# H0FR9.net
KiCad netlist of a schematic drawn in EAGLE
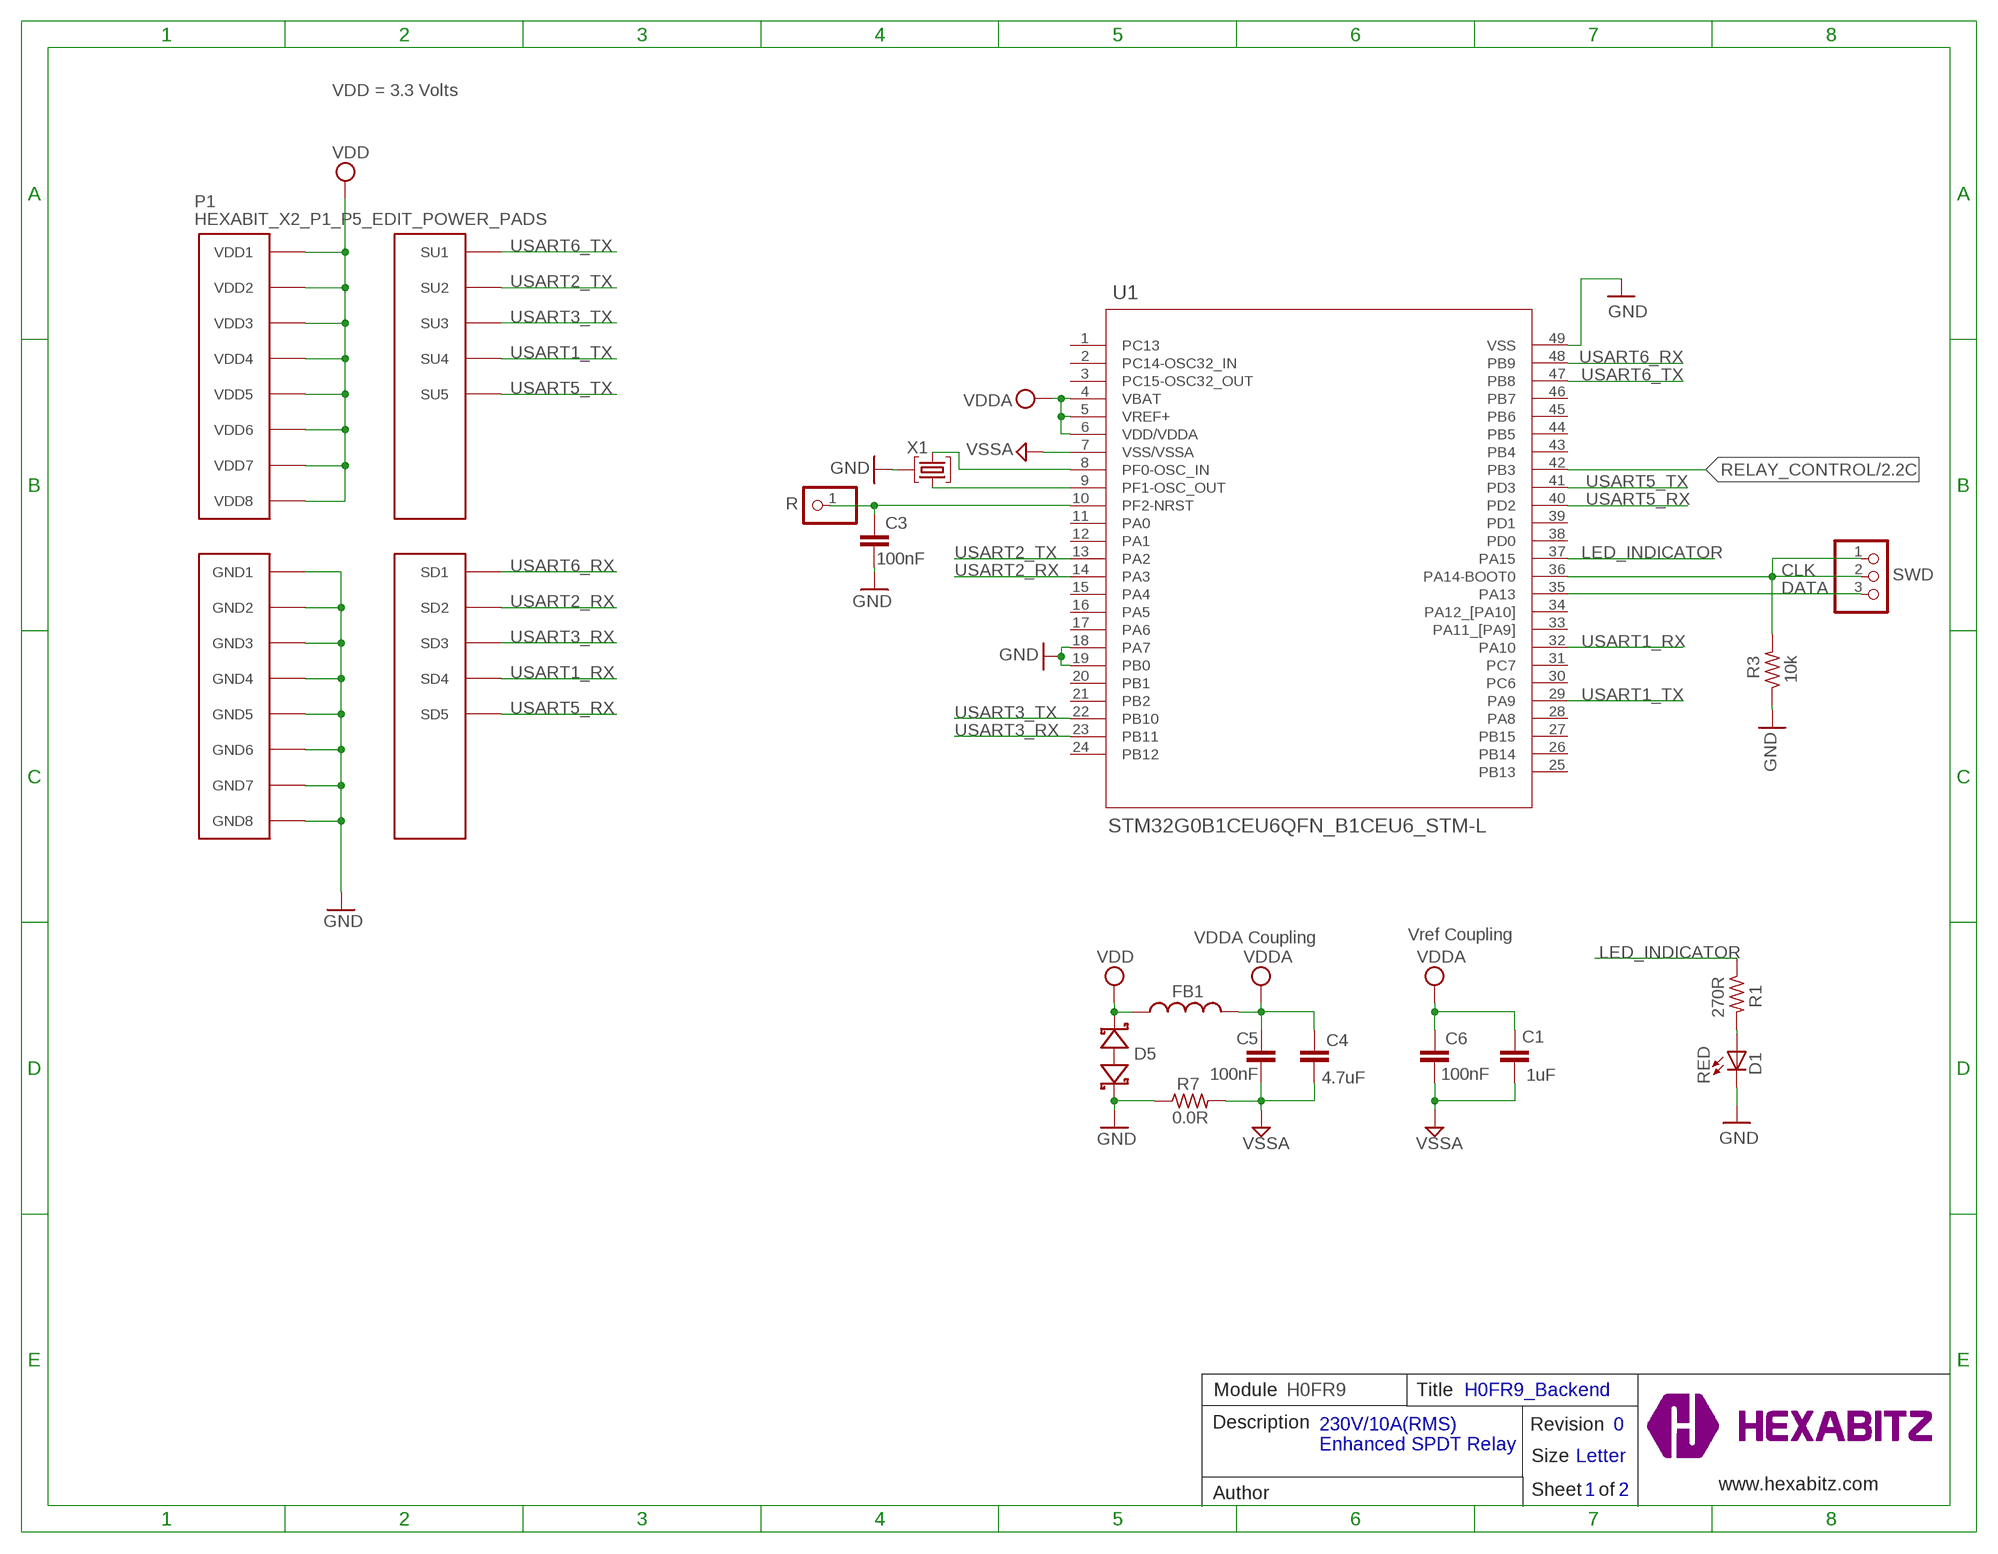
[diagram p0: schematic, sheet 1]
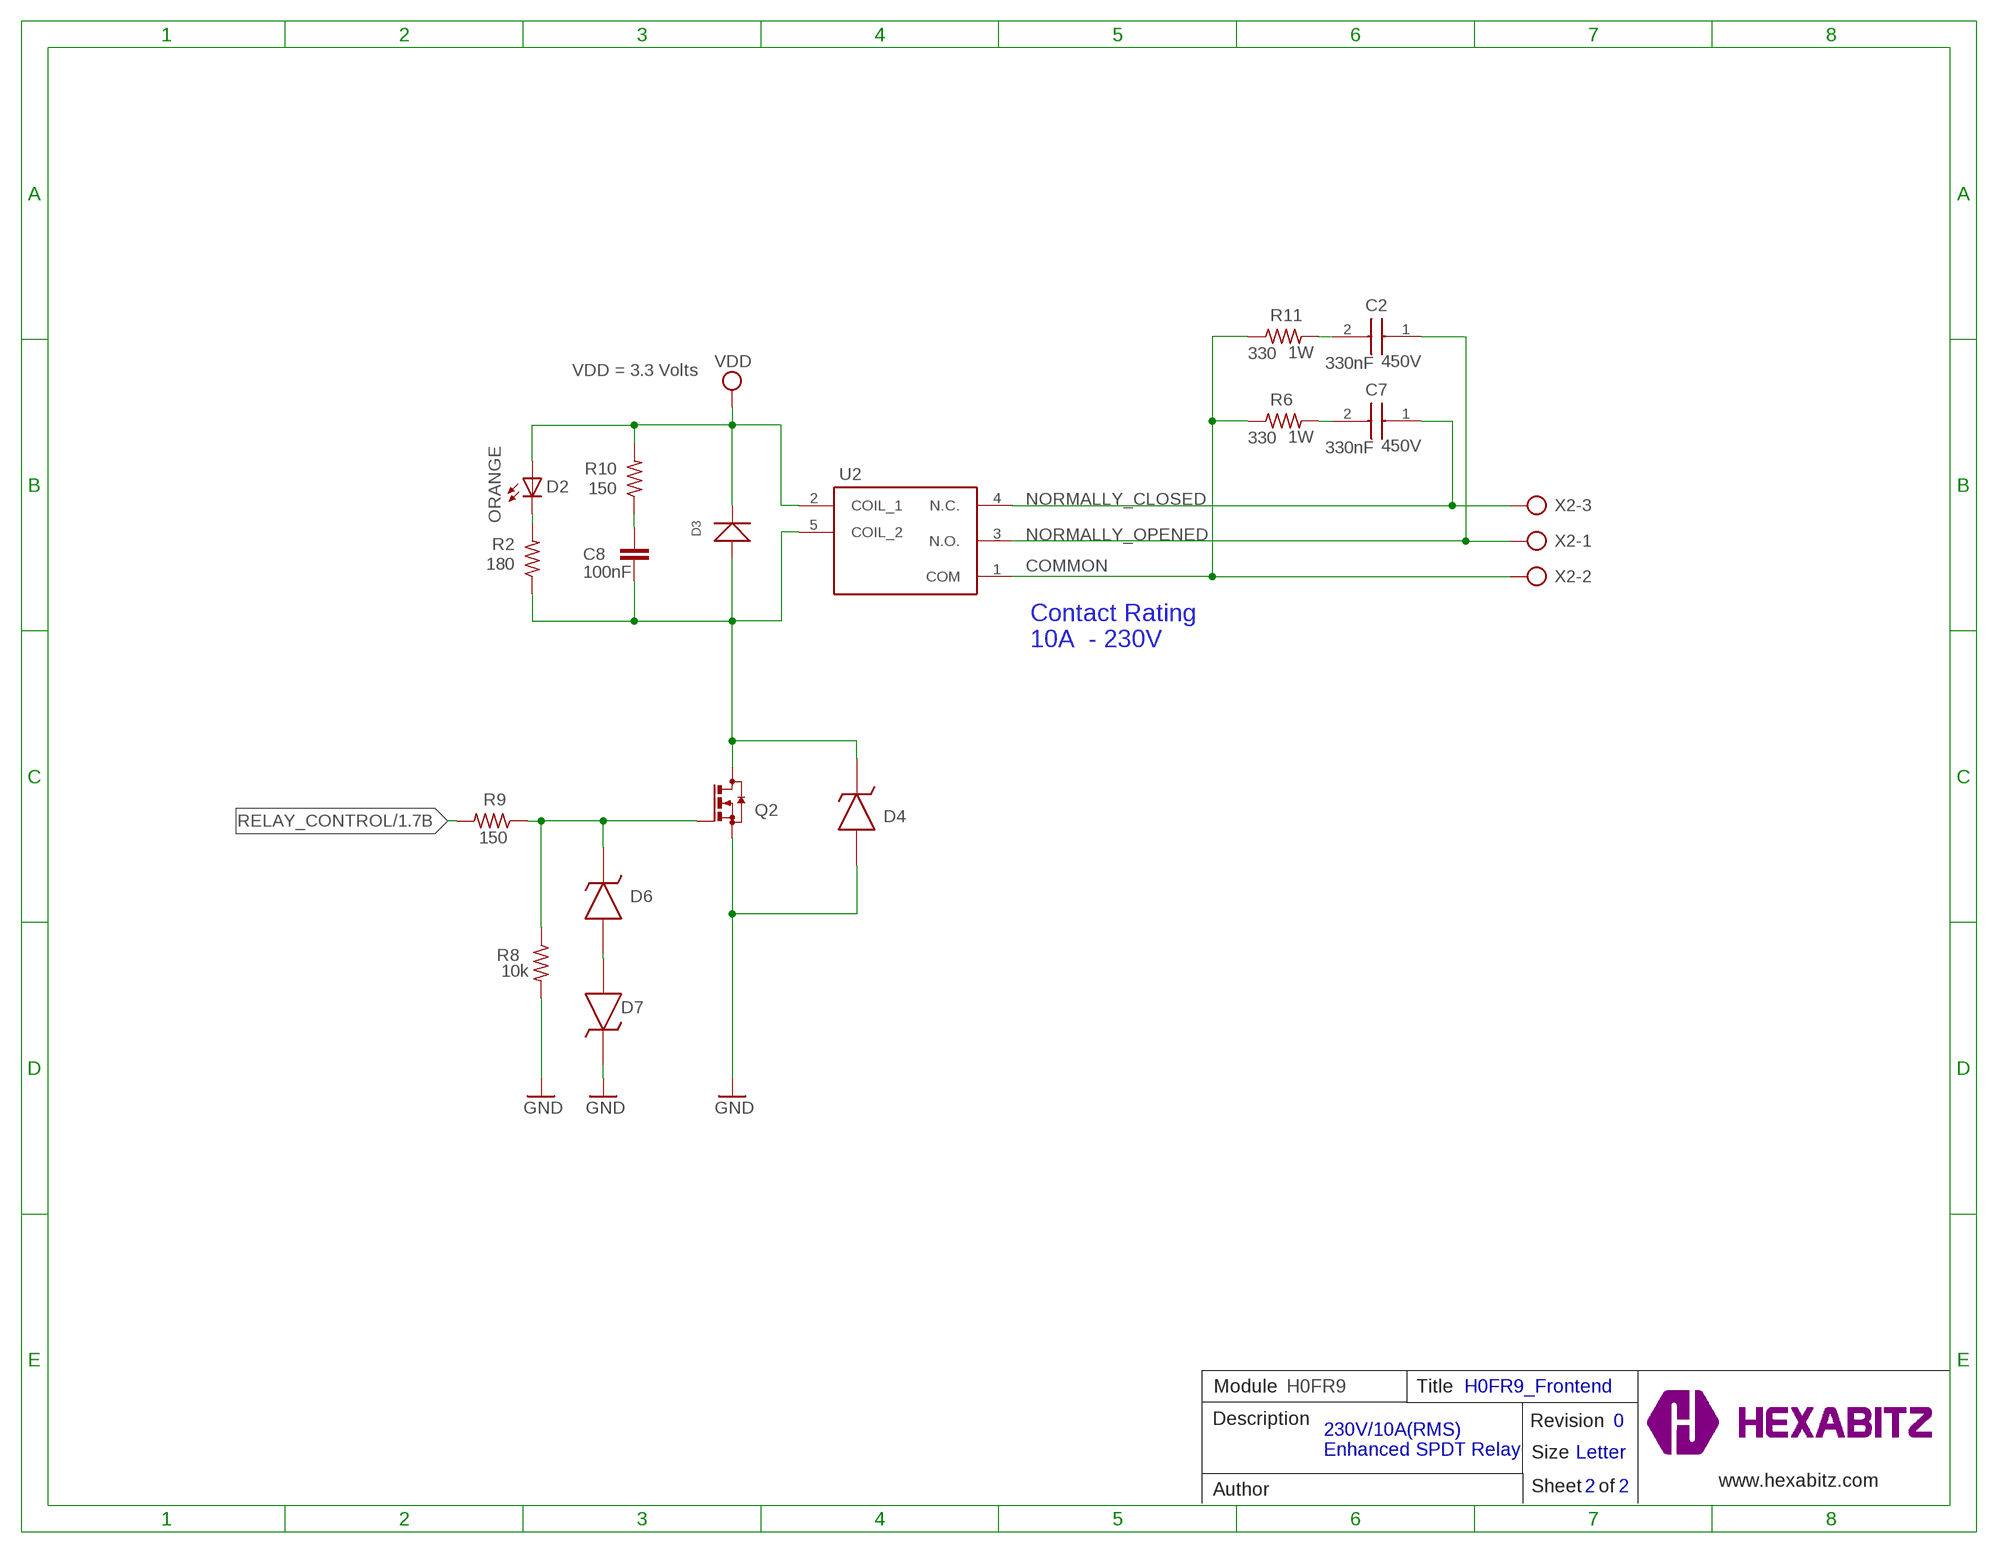
[diagram p1: schematic, sheet 2]

(export (version "E")
  (design (tool "Eeschema 10.0.6"))
  (components
    (comp (ref "C2")
      (value "330nF")
      (footprint "eagle-import:B32922Q_(18_X_8.5)")
      (fields
        (field (name "MANUFACTURER_PART_NUMBER") "B32922Q3334K000")
        (field (name "MOUSER_PART_NUMBER") "871-B32922Q3334K000")
        (field (name "VOLTAAGE") "450V")
      )
      (libsource (lib "eagle-import") (part "B32922Q3334K000"))
    )
    (comp (ref "C7")
      (value "330nF")
      (footprint "eagle-import:B32922Q_(18_X_8.5)")
      (fields
        (field (name "MANUFACTURER_PART_NUMBER") "B32922Q3334K000")
        (field (name "MOUSER_PART_NUMBER") "871-B32922Q3334K000")
        (field (name "VOLTAAGE") "450V")
      )
      (libsource (lib "eagle-import") (part "B32922Q3334K000"))
    )
    (comp (ref "C8")
      (value "100nF")
      (footprint "eagle-import:C-0603")
      (fields
        (field (name "CAPACITANCE") "100nF")
        (field (name "MFN") "KEMET")
        (field (name "MPN") "C0603C104K8RACTU")
        (field (name "OCTOPART_URL") "https://octopart.com/c0603c104k8ractu-kemet-145075?r=sp&s=9bS9ASSwSEqMCE9KBEQZ0g")
        (field (name "TOLERANCE") "10%")
        (field (name "VOLTAGE_RATING") "10V")
      )
      (libsource (lib "eagle-import") (part "C-0603"))
    )
    (comp (ref "D2")
      (value "ORANGE")
      (footprint "eagle-import:VLMS1300-GS08")
      (fields
        (field (name "MPN") "VLMS1300-GS08")
        (field (name "COULOR") "ORANGE")
        (field (name "MFN") "Vishay ")
        (field (name "MPN_1") "VLMY1300-GS08")
        (field (name "OCTOPART_URL") "https://octopart.com/vlmy1300-gs08-vishay-21709204")
      )
      (libsource (lib "eagle-import") (part "Hexabitz_VLMS1300-GS08"))
    )
    (comp (ref "D3")
      (value "40V 300MA")
      (footprint "eagle-import:SOD-323")
      (fields (field (name "MPN") "BAT54JFILM"))
      (libsource (lib "eagle-import") (part "BAT54JFILM_SOD-323"))
    )
    (comp (ref "D4")
      (value "MMSZ4705T1GMMSZ4705T1G")
      (footprint "eagle-import:DIO_MMSZ4700T1G")
      (fields (field (name "MPN") "MMSZ4705T1G"))
      (libsource (lib "eagle-import") (part "MMSZ4705T1GMMSZ4705T1G"))
    )
    (comp (ref "D6")
      (value "MMSZ4705T1GMMSZ4705T1G")
      (footprint "eagle-import:DIO_MMSZ4700T1G")
      (fields (field (name "MPN") "MMSZ5231BT3G"))
      (libsource (lib "eagle-import") (part "MMSZ4705T1GMMSZ4705T1G"))
    )
    (comp (ref "D7")
      (value "MMSZ4705T1GMMSZ4705T1G")
      (footprint "eagle-import:DIO_MMSZ4700T1G")
      (fields (field (name "MPN") "MMSZ5231BT3G"))
      (libsource (lib "eagle-import") (part "MMSZ4705T1GMMSZ4705T1G"))
    )
    (comp (ref "Q2")
      (value "BSS123")
      (footprint "eagle-import:SOT23")
      (libsource (lib "eagle-import") (part "BSS123"))
    )
    (comp (ref "R2")
      (value "180")
      (footprint "eagle-import:R-0603")
      (fields
        (field (name "MFN") "Panasonic")
        (field (name "MPN") "ERJ-3GEYJ181V")
        (field (name "OCTOPART_URL") "https://octopart.com/erj-3geyj181v-panasonic-55403673")
        (field (name "RESISTANCE") "180.0 Ω")
        (field (name "TOLERANCE") "±5%")
      )
      (libsource (lib "eagle-import") (part "R-0603"))
    )
    (comp (ref "R6")
      (value "330")
      (footprint "eagle-import:R2512")
      (fields (field (name "MPN") "RMCF2512JT330R") (field (name "POWER") "1W"))
      (libsource (lib "eagle-import") (part "R-US_R2512"))
    )
    (comp (ref "R8")
      (value "10k")
      (footprint "eagle-import:R-0603")
      (fields
        (field (name "MFN") "Yageo")
        (field (name "MPN") "RC0603JR-07680KL")
        (field (name "OCTOPART_URL") "https://octopart.com/rc0603jr-07680kl-yageo-40953169?r=sp")
        (field (name "RESISTANCE") "680K Ohm")
        (field (name "TOLERANCE") "5%")
      )
      (libsource (lib "eagle-import") (part "R-0603"))
    )
    (comp (ref "R9")
      (value "150")
      (footprint "eagle-import:R-0603")
      (fields
        (field (name "MFN") "Yageo")
        (field (name "MPN") "RC0603JR-07680KL")
        (field (name "OCTOPART_URL") "https://octopart.com/rc0603jr-07680kl-yageo-40953169?r=sp")
        (field (name "RESISTANCE") "680K Ohm")
        (field (name "TOLERANCE") "5%")
      )
      (libsource (lib "eagle-import") (part "R-0603"))
    )
    (comp (ref "R10")
      (value "150")
      (footprint "eagle-import:R-0603")
      (fields
        (field (name "MFN") "Yageo")
        (field (name "MPN") "RC0603JR-07680KL")
        (field (name "OCTOPART_URL") "https://octopart.com/rc0603jr-07680kl-yageo-40953169?r=sp")
        (field (name "RESISTANCE") "680K Ohm")
        (field (name "TOLERANCE") "5%")
      )
      (libsource (lib "eagle-import") (part "R-0603"))
    )
    (comp (ref "R11")
      (value "330")
      (footprint "eagle-import:R2512")
      (fields (field (name "MPN") "RMCF2512JT330R") (field (name "POWER") "1W"))
      (libsource (lib "eagle-import") (part "R-US_R2512"))
    )
    (comp (ref "U2")
      (value "G5LE-14_DC3")
      (footprint "eagle-import:G5LE-14_SPDT")
      (fields
        (field (name "MANUFACTURER_PART_NUMBER") "G5LE-14 DC3")
        (field (name "MOUSER_PART_NUMBER") "653-G5LE-14DC3")
      )
      (libsource (lib "eagle-import") (part "G5LE-14_DC3"))
    )
    (comp (ref "X2")
      (value "AK300/3")
      (footprint "eagle-import:AK300_3")
      (fields (field (name "MPN") "1715734"))
      (libsource (lib "eagle-import") (part "AK300/3"))
    )
    (comp (ref "C1")
      (value "1uF")
      (footprint "eagle-import:C-0805")
      (fields
        (field (name "CAPACITANCE") "1.00uF")
        (field (name "MFN") "Yageo")
        (field (name "MPN") "CC0805KKX7R7BB105")
        (field (name "OCTOPART_URL") "https://octopart.com/cc0805kkx7r7bb105-yageo-8376555?r=sp&s=YKl1wwtkROau_X5nniH2ig")
        (field (name "TOLERANCE") "10%")
        (field (name "VOLTAGE_RATING") "16V")
      )
      (libsource (lib "eagle-import") (part "C-0805"))
    )
    (comp (ref "C3")
      (value "100nF")
      (footprint "eagle-import:C-0603")
      (libsource (lib "eagle-import") (part "C-0603"))
    )
    (comp (ref "C4")
      (value "4.7uF")
      (footprint "eagle-import:C-0805")
      (fields
        (field (name "CAPACITANCE") "4.7uF")
        (field (name "MFN") "Murata")
        (field (name "MPN") "GRM21BC81E475KA12L")
        (field (name "OCTOPART_URL") "https://octopart.com/grm21bc81e475ka12l-murata-10331911?r=sp&s=RY3qZSD8T6mG6TC9CHI5qQ")
        (field (name "TOLERANCE") "10%")
        (field (name "VOLTAGE_RATING") "25V")
      )
      (libsource (lib "eagle-import") (part "C-0805"))
    )
    (comp (ref "C5")
      (value "100nF")
      (footprint "eagle-import:C-0603")
      (libsource (lib "eagle-import") (part "C-0603"))
    )
    (comp (ref "C6")
      (value "100nF")
      (footprint "eagle-import:C-0603")
      (fields
        (field (name "CAPACITANCE") "100nF")
        (field (name "MFN") "KEMET")
        (field (name "MPN") "C0603C104K8RACTU")
        (field (name "OCTOPART_URL") "https://octopart.com/c0603c104k8ractu-kemet-145075?r=sp&s=9bS9ASSwSEqMCE9KBEQZ0g")
        (field (name "TOLERANCE") "10%")
        (field (name "VOLTAGE_RATING") "10V")
      )
      (libsource (lib "eagle-import") (part "C-0603"))
    )
    (comp (ref "D1")
      (value "RED")
      (footprint "eagle-import:VLMS1300-GS08")
      (fields
        (field (name "MPN") "VLMS1300-GS08")
        (field (name "MFN") "Vishay")
        (field (name "MPN_1") "VLMS1300-GS08")
        (field (name "OCTOPART_URL") "https://octopart.com/vlms1300-gs08-vishay-21709201?r=sp&s=_gcP4_q8T1SC6PJQPTQ9yA")
      )
      (libsource (lib "eagle-import") (part "VLMS1300-GS08"))
    )
    (comp (ref "D5")
      (value "BOURNS_CDSOD323-T03SCBOURNS_CDSOD323-T03SC_0_0")
      (footprint "eagle-import:BOURNS_CDSOD323-T03SC_0")
      (fields (field (name "MPN") "CDSOD323-T03SC"))
      (libsource (lib "eagle-import") (part "BOURNS_CDSOD323-T03SCBOURNS_CDSOD323-T03SC_0_0"))
    )
    (comp (ref "FB1")
      (value "FB-0603")
      (footprint "eagle-import:FB-0603")
      (libsource (lib "eagle-import") (part "FB-0603"))
    )
    (comp (ref "P1")
      (value "HEXABIT_X2_P1_P5_EDIT_POWER_PADS")
      (footprint "eagle-import:HEXABIT_X2_P1_P5_EDIT_POWER_PADS")
      (libsource (lib "eagle-import") (part "HEXABIT_X2_P1_P5_EDIT_POWER_PADS"))
    )
    (comp (ref "R")
      (value "R")
      (footprint "eagle-import:1X01")
      (fields (field (name "MPN") "87227-1"))
      (libsource (lib "eagle-import") (part "PINHD-1X1"))
    )
    (comp (ref "R1")
      (value "270R")
      (footprint "eagle-import:R-0603")
      (libsource (lib "eagle-import") (part "R-0603"))
    )
    (comp (ref "R3")
      (value "10k")
      (footprint "eagle-import:R-0603")
      (fields
        (field (name "MFN") "Yageo")
        (field (name "MPN") "RC0603JR-0710KL")
        (field (name "OCTOPART_URL") "https://octopart.com/search?q=RC0603JR-0710KL&start=0")
        (field (name "RESISTANCE") "10.0K Ohm")
        (field (name "TOLERANCE") "5%")
      )
      (libsource (lib "eagle-import") (part "R-0603"))
    )
    (comp (ref "R7")
      (value "0.0R")
      (footprint "eagle-import:R-0603")
      (libsource (lib "eagle-import") (part "R-0603"))
    )
    (comp (ref "SWD")
      (value "PINHD-1X3SWD")
      (footprint "eagle-import:SWD")
      (libsource (lib "eagle-import") (part "PINHD-1X3SWD"))
    )
    (comp (ref "TRIMBLE-LOGO2")
      (value "HEXA-LOGO")
      (footprint "eagle-import:HEXA-LOGO")
      (libsource (lib "eagle-import") (part "HEXA-LOGO"))
    )
    (comp (ref "U1")
      (value "STM32G0B1CEU6QFN_B1CEU6_STM-L")
      (footprint "eagle-import:QFN_B1CEU6_STM-L")
      (fields
        (field (name "MANUFACTURER_PART_NUMBER") "STM32G0B1CEU6")
        (field (name "COPYRIGHT") "Copyright (C) 2021 Ultra Librarian. All rights reserved.")
      )
      (libsource (lib "eagle-import") (part "STM32G0B1CEU6QFN_B1CEU6_STM-L"))
    )
    (comp (ref "X1")
      (value "XTALL_CSTCE8M00G52")
      (footprint "eagle-import:XTALL_CSTCE8M00G52")
      (fields (field (name "MPN") "CSTCE8M00G52Z-R0"))
      (libsource (lib "eagle-import") (part "XTALL_CSTCE8M00G52"))
    )
  )
  (nets
    (net (code "1") (name "CLK") (class "Default")
      (node (ref "R3") (pin "2") (pinfunction "2_2") (pintype "passive"))
      (node (ref "SWD") (pin "1") (pinfunction "1_1") (pintype "passive"))
      (node (ref "SWD") (pin "2") (pinfunction "2_2") (pintype "passive"))
      (node (ref "U1") (pin "36") (pinfunction "PA14-BOOT0_36") (pintype "bidirectional"))
    )
    (net (code "2") (name "COMMON") (class "Default")
      (node (ref "R11") (pin "1") (pinfunction "1_1") (pintype "passive"))
      (node (ref "R6") (pin "1") (pinfunction "1_1") (pintype "passive"))
      (node (ref "U2") (pin "1") (pinfunction "COM_1") (pintype "bidirectional"))
      (node (ref "X2") (pin "2") (pinfunction "KL_2") (pintype "passive"))
    )
    (net (code "3") (name "DATA") (class "Default")
      (node (ref "SWD") (pin "3") (pinfunction "3_3") (pintype "passive"))
      (node (ref "U1") (pin "35") (pinfunction "PA13_35") (pintype "bidirectional"))
    )
    (net (code "4") (name "GND") (class "Default")
      (node (ref "C3") (pin "2") (pinfunction "2_2") (pintype "passive"))
      (node (ref "D1") (pin "C") (pinfunction "C_C") (pintype "passive"))
      (node (ref "D4") (pin "A") (pinfunction "A_A") (pintype "bidirectional"))
      (node (ref "D5") (pin "2") (pinfunction "C_2") (pintype "passive"))
      (node (ref "D7") (pin "K") (pinfunction "K_K") (pintype "bidirectional"))
      (node (ref "P1") (pin "PAD_PD11") (pinfunction "GND1_PAD_PD11") (pintype "power_in"))
      (node (ref "P1") (pin "PAD_PD12") (pinfunction "GND2_PAD_PD12") (pintype "power_in"))
      (node (ref "P1") (pin "PAD_PD13") (pinfunction "GND3_PAD_PD13") (pintype "power_in"))
      (node (ref "P1") (pin "PAD_PD14") (pinfunction "GND4_PAD_PD14") (pintype "power_in"))
      (node (ref "P1") (pin "PAD_PD17") (pinfunction "GND5_PAD_PD17") (pintype "power_in"))
      (node (ref "P1") (pin "PAD_PD18") (pinfunction "GND6_PAD_PD18") (pintype "power_in"))
      (node (ref "P1") (pin "PAD_PD19") (pinfunction "GND7_PAD_PD19") (pintype "power_in"))
      (node (ref "P1") (pin "PAD_PD20") (pinfunction "GND8_PAD_PD20") (pintype "power_in"))
      (node (ref "Q2") (pin "2") (pinfunction "S_2") (pintype "passive"))
      (node (ref "R3") (pin "1") (pinfunction "1_1") (pintype "passive"))
      (node (ref "R7") (pin "1") (pinfunction "1_1") (pintype "passive"))
      (node (ref "R8") (pin "2") (pinfunction "2_2") (pintype "passive"))
      (node (ref "U1") (pin "18") (pinfunction "PA7_18") (pintype "bidirectional"))
      (node (ref "U1") (pin "19") (pinfunction "PB0_19") (pintype "bidirectional"))
      (node (ref "U1") (pin "49") (pinfunction "VSS_49") (pintype "passive"))
      (node (ref "X1") (pin "P$2") (pinfunction "2_P$2") (pintype "passive"))
    )
    (net (code "5") (name "LED_INDICATOR") (class "Default")
      (node (ref "R1") (pin "1") (pinfunction "1_1") (pintype "passive"))
      (node (ref "U1") (pin "37") (pinfunction "PA15_37") (pintype "bidirectional"))
    )
    (net (code "6") (name "NORMALLY_CLOSED") (class "Default")
      (node (ref "C7") (pin "1") (pinfunction "1_1") (pintype "bidirectional"))
      (node (ref "U2") (pin "4") (pinfunction "N.C._4") (pintype "bidirectional"))
      (node (ref "X2") (pin "3") (pinfunction "KL_3") (pintype "passive"))
    )
    (net (code "7") (name "NORMALLY_OPENED") (class "Default")
      (node (ref "C2") (pin "1") (pinfunction "1_1") (pintype "bidirectional"))
      (node (ref "U2") (pin "3") (pinfunction "N.O._3") (pintype "bidirectional"))
      (node (ref "X2") (pin "1") (pinfunction "KL_1") (pintype "passive"))
    )
    (net (code "8") (name "Net-(C2-Pad2)") (class "Default")
      (node (ref "C2") (pin "2") (pinfunction "2_2") (pintype "bidirectional"))
      (node (ref "R11") (pin "2") (pinfunction "2_2") (pintype "passive"))
    )
    (net (code "9") (name "Net-(C7-Pad2)") (class "Default")
      (node (ref "C7") (pin "2") (pinfunction "2_2") (pintype "bidirectional"))
      (node (ref "R6") (pin "2") (pinfunction "2_2") (pintype "passive"))
    )
    (net (code "10") (name "Net-(C8-Pad1)") (class "Default")
      (node (ref "C8") (pin "1") (pinfunction "1_1") (pintype "passive"))
      (node (ref "R10") (pin "1") (pinfunction "1_1") (pintype "passive"))
    )
    (net (code "11") (name "Net-(D1-PadA)") (class "Default")
      (node (ref "D1") (pin "A") (pinfunction "A_A") (pintype "passive"))
      (node (ref "R1") (pin "2") (pinfunction "2_2") (pintype "passive"))
    )
    (net (code "12") (name "Net-(D2-PadC)") (class "Default")
      (node (ref "D2") (pin "C") (pinfunction "C_C") (pintype "passive"))
      (node (ref "R2") (pin "2") (pinfunction "2_2") (pintype "passive"))
    )
    (net (code "13") (name "Net-(D6-PadA)") (class "Default")
      (node (ref "D6") (pin "A") (pinfunction "A_A") (pintype "bidirectional"))
      (node (ref "D7") (pin "A") (pinfunction "A_A") (pintype "bidirectional"))
    )
    (net (code "14") (name "Net-(Q2-D)") (class "Default")
      (node (ref "C8") (pin "2") (pinfunction "2_2") (pintype "passive"))
      (node (ref "D3") (pin "+") (pinfunction "+_+") (pintype "passive"))
      (node (ref "D4") (pin "K") (pinfunction "K_K") (pintype "bidirectional"))
      (node (ref "Q2") (pin "3") (pinfunction "D_3") (pintype "passive"))
      (node (ref "R2") (pin "1") (pinfunction "1_1") (pintype "passive"))
      (node (ref "U2") (pin "5") (pinfunction "COIL_2_5") (pintype "bidirectional"))
    )
    (net (code "15") (name "Net-(Q2-G)") (class "Default")
      (node (ref "D6") (pin "K") (pinfunction "K_K") (pintype "bidirectional"))
      (node (ref "Q2") (pin "1") (pinfunction "G_1") (pintype "passive"))
      (node (ref "R8") (pin "1") (pinfunction "1_1") (pintype "passive"))
      (node (ref "R9") (pin "1") (pinfunction "1_1") (pintype "passive"))
    )
    (net (code "16") (name "Net-(U1-PF0-OSC_IN)") (class "Default")
      (node (ref "U1") (pin "8") (pinfunction "PF0-OSC_IN_8") (pintype "bidirectional"))
      (node (ref "X1") (pin "P$3") (pinfunction "3_P$3") (pintype "passive"))
    )
    (net (code "17") (name "Net-(U1-PF1-OSC_OUT)") (class "Default")
      (node (ref "U1") (pin "9") (pinfunction "PF1-OSC_OUT_9") (pintype "output"))
      (node (ref "X1") (pin "P$1") (pinfunction "1_P$1") (pintype "passive"))
    )
    (net (code "18") (name "Net-(U1-PF2-NRST)") (class "Default")
      (node (ref "C3") (pin "1") (pinfunction "1_1") (pintype "passive"))
      (node (ref "R") (pin "1") (pinfunction "1_1") (pintype "passive"))
      (node (ref "U1") (pin "10") (pinfunction "PF2-NRST_10") (pintype "bidirectional"))
    )
    (net (code "19") (name "RELAY_CONTROL") (class "Default")
      (node (ref "R9") (pin "2") (pinfunction "2_2") (pintype "passive"))
      (node (ref "U1") (pin "42") (pinfunction "PB3_42") (pintype "bidirectional"))
    )
    (net (code "20") (name "USART1_RX") (class "Default")
      (node (ref "P1") (pin "PAD_PD4") (pinfunction "SD4_PAD_PD4") (pintype "bidirectional"))
      (node (ref "U1") (pin "32") (pinfunction "PA10_32") (pintype "bidirectional"))
    )
    (net (code "21") (name "USART1_TX") (class "Default")
      (node (ref "P1") (pin "PAD_PU4") (pinfunction "SU4_PAD_PU4") (pintype "bidirectional"))
      (node (ref "U1") (pin "29") (pinfunction "PA9_29") (pintype "bidirectional"))
    )
    (net (code "22") (name "USART2_RX") (class "Default")
      (node (ref "P1") (pin "PAD_PD2") (pinfunction "SD2_PAD_PD2") (pintype "bidirectional"))
      (node (ref "U1") (pin "14") (pinfunction "PA3_14") (pintype "bidirectional"))
    )
    (net (code "23") (name "USART2_TX") (class "Default")
      (node (ref "P1") (pin "PAD_PU2") (pinfunction "SU2_PAD_PU2") (pintype "bidirectional"))
      (node (ref "U1") (pin "13") (pinfunction "PA2_13") (pintype "bidirectional"))
    )
    (net (code "24") (name "USART3_RX") (class "Default")
      (node (ref "P1") (pin "PAD_PD3") (pinfunction "SD3_PAD_PD3") (pintype "bidirectional"))
      (node (ref "U1") (pin "23") (pinfunction "PB11_23") (pintype "bidirectional"))
    )
    (net (code "25") (name "USART3_TX") (class "Default")
      (node (ref "P1") (pin "PAD_PU3") (pinfunction "SU3_PAD_PU3") (pintype "bidirectional"))
      (node (ref "U1") (pin "22") (pinfunction "PB10_22") (pintype "bidirectional"))
    )
    (net (code "26") (name "USART5_RX") (class "Default")
      (node (ref "P1") (pin "PAD_PD5") (pinfunction "SD5_PAD_PD5") (pintype "bidirectional"))
      (node (ref "U1") (pin "40") (pinfunction "PD2_40") (pintype "bidirectional"))
    )
    (net (code "27") (name "USART5_TX") (class "Default")
      (node (ref "P1") (pin "PAD_PU5") (pinfunction "SU5_PAD_PU5") (pintype "bidirectional"))
      (node (ref "U1") (pin "41") (pinfunction "PD3_41") (pintype "bidirectional"))
    )
    (net (code "28") (name "USART6_RX") (class "Default")
      (node (ref "P1") (pin "PAD_PD1") (pinfunction "SD1_PAD_PD1") (pintype "bidirectional"))
      (node (ref "U1") (pin "48") (pinfunction "PB9_48") (pintype "bidirectional"))
    )
    (net (code "29") (name "USART6_TX") (class "Default")
      (node (ref "P1") (pin "PAD_PU1") (pinfunction "SU1_PAD_PU1") (pintype "bidirectional"))
      (node (ref "U1") (pin "47") (pinfunction "PB8_47") (pintype "bidirectional"))
    )
    (net (code "30") (name "VDD") (class "Default")
      (node (ref "D2") (pin "A") (pinfunction "A_A") (pintype "passive"))
      (node (ref "D3") (pin "-") (pinfunction "-_-") (pintype "passive"))
      (node (ref "D5") (pin "1") (pinfunction "A_1") (pintype "passive"))
      (node (ref "FB1") (pin "1") (pinfunction "1_1") (pintype "passive"))
      (node (ref "P1") (pin "PAD_PU11") (pinfunction "VDD1_PAD_PU11") (pintype "power_in"))
      (node (ref "P1") (pin "PAD_PU12") (pinfunction "VDD2_PAD_PU12") (pintype "power_in"))
      (node (ref "P1") (pin "PAD_PU13") (pinfunction "VDD3_PAD_PU13") (pintype "power_in"))
      (node (ref "P1") (pin "PAD_PU14") (pinfunction "VDD4_PAD_PU14") (pintype "power_in"))
      (node (ref "P1") (pin "PAD_PU17") (pinfunction "VDD5_PAD_PU17") (pintype "power_in"))
      (node (ref "P1") (pin "PAD_PU18") (pinfunction "VDD6_PAD_PU18") (pintype "power_in"))
      (node (ref "P1") (pin "PAD_PU19") (pinfunction "VDD7_PAD_PU19") (pintype "power_in"))
      (node (ref "P1") (pin "PAD_PU20") (pinfunction "VDD8_PAD_PU20") (pintype "power_in"))
      (node (ref "R10") (pin "2") (pinfunction "2_2") (pintype "passive"))
      (node (ref "U2") (pin "2") (pinfunction "COIL_1_2") (pintype "bidirectional"))
    )
    (net (code "31") (name "VDDA") (class "Default")
      (node (ref "C1") (pin "1") (pinfunction "1_1") (pintype "passive"))
      (node (ref "C4") (pin "1") (pinfunction "1_1") (pintype "passive"))
      (node (ref "C5") (pin "1") (pinfunction "1_1") (pintype "passive"))
      (node (ref "C6") (pin "1") (pinfunction "1_1") (pintype "passive"))
      (node (ref "FB1") (pin "2") (pinfunction "2_2") (pintype "passive"))
      (node (ref "U1") (pin "4") (pinfunction "VBAT_4") (pintype "passive"))
      (node (ref "U1") (pin "5") (pinfunction "VREF+_5") (pintype "power_in"))
      (node (ref "U1") (pin "6") (pinfunction "VDD/VDDA_6") (pintype "power_in"))
    )
    (net (code "32") (name "VSSA") (class "Default")
      (node (ref "C1") (pin "2") (pinfunction "2_2") (pintype "passive"))
      (node (ref "C4") (pin "2") (pinfunction "2_2") (pintype "passive"))
      (node (ref "C5") (pin "2") (pinfunction "2_2") (pintype "passive"))
      (node (ref "C6") (pin "2") (pinfunction "2_2") (pintype "passive"))
      (node (ref "R7") (pin "2") (pinfunction "2_2") (pintype "passive"))
      (node (ref "U1") (pin "7") (pinfunction "VSS/VSSA_7") (pintype "passive"))
    )
    (net (code "33") (name "unconnected-(U1-PA0-Pad11)") (class "Default")
      (node (ref "U1") (pin "11") (pinfunction "PA0_11") (pintype "bidirectional"))
    )
    (net (code "34") (name "unconnected-(U1-PA1-Pad12)") (class "Default")
      (node (ref "U1") (pin "12") (pinfunction "PA1_12") (pintype "bidirectional"))
    )
    (net (code "35") (name "unconnected-(U1-PA4-Pad15)") (class "Default")
      (node (ref "U1") (pin "15") (pinfunction "PA4_15") (pintype "bidirectional"))
    )
    (net (code "36") (name "unconnected-(U1-PA5-Pad16)") (class "Default")
      (node (ref "U1") (pin "16") (pinfunction "PA5_16") (pintype "bidirectional"))
    )
    (net (code "37") (name "unconnected-(U1-PA6-Pad17)") (class "Default")
      (node (ref "U1") (pin "17") (pinfunction "PA6_17") (pintype "bidirectional"))
    )
    (net (code "38") (name "unconnected-(U1-PA8-Pad28)") (class "Default")
      (node (ref "U1") (pin "28") (pinfunction "PA8_28") (pintype "bidirectional"))
    )
    (net (code "39") (name "unconnected-(U1-PA11_[PA9]-Pad33)") (class "Default")
      (node (ref "U1") (pin "33") (pinfunction "PA11_[PA9]_33") (pintype "bidirectional"))
    )
    (net (code "40") (name "unconnected-(U1-PA12_[PA10]-Pad34)") (class "Default")
      (node (ref "U1") (pin "34") (pinfunction "PA12_[PA10]_34") (pintype "bidirectional"))
    )
    (net (code "41") (name "unconnected-(U1-PB1-Pad20)") (class "Default")
      (node (ref "U1") (pin "20") (pinfunction "PB1_20") (pintype "bidirectional"))
    )
    (net (code "42") (name "unconnected-(U1-PB2-Pad21)") (class "Default")
      (node (ref "U1") (pin "21") (pinfunction "PB2_21") (pintype "bidirectional"))
    )
    (net (code "43") (name "unconnected-(U1-PB4-Pad43)") (class "Default")
      (node (ref "U1") (pin "43") (pinfunction "PB4_43") (pintype "bidirectional"))
    )
    (net (code "44") (name "unconnected-(U1-PB5-Pad44)") (class "Default")
      (node (ref "U1") (pin "44") (pinfunction "PB5_44") (pintype "bidirectional"))
    )
    (net (code "45") (name "unconnected-(U1-PB6-Pad45)") (class "Default")
      (node (ref "U1") (pin "45") (pinfunction "PB6_45") (pintype "bidirectional"))
    )
    (net (code "46") (name "unconnected-(U1-PB7-Pad46)") (class "Default")
      (node (ref "U1") (pin "46") (pinfunction "PB7_46") (pintype "bidirectional"))
    )
    (net (code "47") (name "unconnected-(U1-PB12-Pad24)") (class "Default")
      (node (ref "U1") (pin "24") (pinfunction "PB12_24") (pintype "bidirectional"))
    )
    (net (code "48") (name "unconnected-(U1-PB13-Pad25)") (class "Default")
      (node (ref "U1") (pin "25") (pinfunction "PB13_25") (pintype "bidirectional"))
    )
    (net (code "49") (name "unconnected-(U1-PB14-Pad26)") (class "Default")
      (node (ref "U1") (pin "26") (pinfunction "PB14_26") (pintype "bidirectional"))
    )
    (net (code "50") (name "unconnected-(U1-PB15-Pad27)") (class "Default")
      (node (ref "U1") (pin "27") (pinfunction "PB15_27") (pintype "bidirectional"))
    )
    (net (code "51") (name "unconnected-(U1-PC6-Pad30)") (class "Default")
      (node (ref "U1") (pin "30") (pinfunction "PC6_30") (pintype "bidirectional"))
    )
    (net (code "52") (name "unconnected-(U1-PC7-Pad31)") (class "Default")
      (node (ref "U1") (pin "31") (pinfunction "PC7_31") (pintype "bidirectional"))
    )
    (net (code "53") (name "unconnected-(U1-PC13-Pad1)") (class "Default")
      (node (ref "U1") (pin "1") (pinfunction "PC13_1") (pintype "bidirectional"))
    )
    (net (code "54") (name "unconnected-(U1-PC14-OSC32_IN-Pad2)") (class "Default")
      (node (ref "U1") (pin "2") (pinfunction "PC14-OSC32_IN_2") (pintype "bidirectional"))
    )
    (net (code "55") (name "unconnected-(U1-PC15-OSC32_OUT-Pad3)") (class "Default")
      (node (ref "U1") (pin "3") (pinfunction "PC15-OSC32_OUT_3") (pintype "output"))
    )
    (net (code "56") (name "unconnected-(U1-PD0-Pad38)") (class "Default")
      (node (ref "U1") (pin "38") (pinfunction "PD0_38") (pintype "bidirectional"))
    )
    (net (code "57") (name "unconnected-(U1-PD1-Pad39)") (class "Default")
      (node (ref "U1") (pin "39") (pinfunction "PD1_39") (pintype "bidirectional"))
    )
  )
)
